# POWER2.net
KiCad netlist of a schematic drawn in Altium Designer
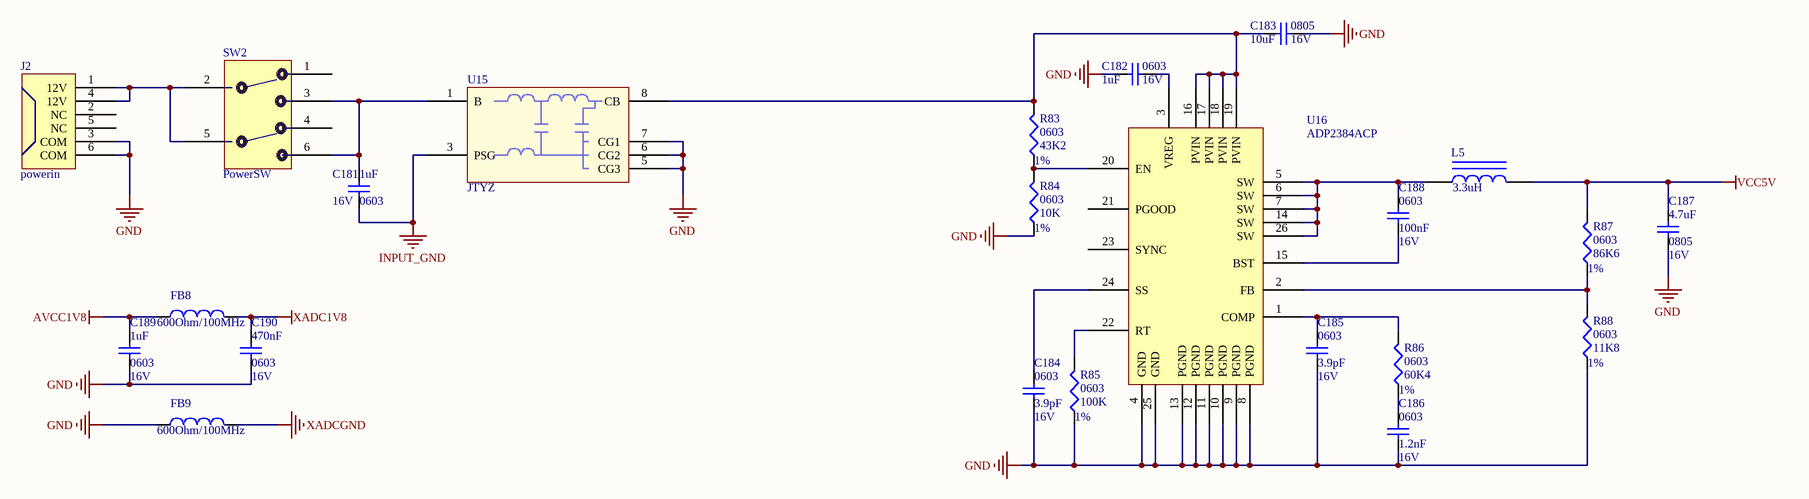
[diagram p0: POWER2.SchDoc]

(export (version "E")
  (design (tool "Eeschema 10.0.6"))
  (components
    (comp (ref "C181")
      (value "1uF")
      (footprint "1608[0603]")
      (description "Capacitor (Semiconductor SIM Model)")
      (fields
        (field (name "PACKAGEREFERENCE") "0603")
        (field (name "V") "16V")
        (field (name "PUBLISHER") "Altium Limited")
      )
      (libsource (lib "Devices") (part "Cap Semi"))
    )
    (comp (ref "C182")
      (value "1uF")
      (footprint "1608[0603]")
      (description "Capacitor (Semiconductor SIM Model)")
      (fields
        (field (name "PACKAGEREFERENCE") "0603")
        (field (name "V") "16V")
        (field (name "PUBLISHER") "Altium Limited")
      )
      (libsource (lib "Devices") (part "Cap Semi"))
    )
    (comp (ref "C183")
      (value "10uF")
      (footprint "2012[0805]")
      (description "Capacitor (Semiconductor SIM Model)")
      (fields
        (field (name "PACKAGEREFERENCE") "0805")
        (field (name "V") "16V")
        (field (name "PUBLISHER") "Altium Limited")
      )
      (libsource (lib "Devices") (part "Cap Semi"))
    )
    (comp (ref "C184")
      (value "3.9pF")
      (footprint "1608[0603]")
      (description "Capacitor (Semiconductor SIM Model)")
      (fields
        (field (name "PACKAGEREFERENCE") "0603")
        (field (name "V") "16V")
        (field (name "PUBLISHER") "Altium Limited")
      )
      (libsource (lib "Devices") (part "Cap Semi"))
    )
    (comp (ref "C185")
      (value "3.9pF")
      (footprint "1608[0603]")
      (description "Capacitor (Semiconductor SIM Model)")
      (fields
        (field (name "PACKAGEREFERENCE") "0603")
        (field (name "V") "16V")
        (field (name "PUBLISHER") "Altium Limited")
      )
      (libsource (lib "Devices") (part "Cap Semi"))
    )
    (comp (ref "C186")
      (value "1.2nF")
      (footprint "1608[0603]")
      (description "Capacitor (Semiconductor SIM Model)")
      (fields
        (field (name "PACKAGEREFERENCE") "0603")
        (field (name "V") "16V")
        (field (name "PUBLISHER") "Altium Limited")
      )
      (libsource (lib "Devices") (part "Cap Semi"))
    )
    (comp (ref "C187")
      (value "4.7uF")
      (footprint "2012[0805]")
      (description "Capacitor (Semiconductor SIM Model)")
      (fields
        (field (name "PACKAGEREFERENCE") "0805")
        (field (name "V") "16V")
        (field (name "PUBLISHER") "Altium Limited")
      )
      (libsource (lib "Devices") (part "Cap Semi"))
    )
    (comp (ref "C188")
      (value "100nF")
      (footprint "1608[0603]")
      (description "Capacitor (Semiconductor SIM Model)")
      (fields
        (field (name "PACKAGEREFERENCE") "0603")
        (field (name "V") "16V")
        (field (name "PUBLISHER") "Altium Limited")
      )
      (libsource (lib "Devices") (part "Cap Semi"))
    )
    (comp (ref "C189")
      (value "1uF")
      (footprint "1608[0603]")
      (description "Capacitor (Semiconductor SIM Model)")
      (fields
        (field (name "PACKAGEREFERENCE") "0603")
        (field (name "V") "16V")
        (field (name "PUBLISHER") "Altium Limited")
      )
      (libsource (lib "Devices") (part "Cap Semi"))
    )
    (comp (ref "C190")
      (value "470nF")
      (footprint "1608[0603]")
      (description "Capacitor (Semiconductor SIM Model)")
      (fields
        (field (name "PACKAGEREFERENCE") "0603")
        (field (name "V") "16V")
        (field (name "PUBLISHER") "Altium Limited")
      )
      (libsource (lib "Devices") (part "Cap Semi"))
    )
    (comp (ref "FB8")
      (value "600Ohm/100MHz")
      (footprint "2012[0805]")
      (description "Inductor")
      (libsource (lib "Miscellaneous Devices") (part "Inductor"))
    )
    (comp (ref "FB9")
      (value "600Ohm/100MHz")
      (footprint "2012[0805]")
      (description "Inductor")
      (libsource (lib "Miscellaneous Devices") (part "Inductor"))
    )
    (comp (ref "J2")
      (value "powerin")
      (footprint "POWER2X3")
      (libsource (lib "Spartan6_LX9_A0") (part "powerin"))
    )
    (comp (ref "L5")
      (value "3.3uH")
      (footprint "SRN4018")
      (description "Magnetic-Core Inductor")
      (fields (field (name "Comment") "Inductor Iron") (field (name "PUBLISHER") "Altium Limited"))
      (libsource (lib "Miscellaneous Devices") (part "Inductor Iron"))
    )
    (comp (ref "R83")
      (value "43K2")
      (footprint "1608[0603]")
      (description "Resistor")
      (fields
        (field (name "PACKAGEREFERENCE") "0603")
        (field (name "AC") "1%")
        (field (name "Comment") "Res3")
        (field (name "PUBLISHER") "Altium Limited")
      )
      (libsource (lib "Miscellaneous Devices") (part "Res3"))
    )
    (comp (ref "R84")
      (value "10K")
      (footprint "1608[0603]")
      (description "Resistor")
      (fields
        (field (name "PACKAGEREFERENCE") "0603")
        (field (name "AC") "1%")
        (field (name "Comment") "Res3")
        (field (name "PUBLISHER") "Altium Limited")
      )
      (libsource (lib "Miscellaneous Devices") (part "Res3"))
    )
    (comp (ref "R85")
      (value "100K")
      (footprint "1608[0603]")
      (description "Resistor")
      (fields
        (field (name "PACKAGEREFERENCE") "0603")
        (field (name "AC") "1%")
        (field (name "Comment") "Res3")
        (field (name "PUBLISHER") "Altium Limited")
      )
      (libsource (lib "Miscellaneous Devices") (part "Res3"))
    )
    (comp (ref "R86")
      (value "60K4")
      (footprint "1608[0603]")
      (description "Resistor")
      (fields
        (field (name "PACKAGEREFERENCE") "0603")
        (field (name "AC") "1%")
        (field (name "Comment") "Res3")
        (field (name "PUBLISHER") "Altium Limited")
      )
      (libsource (lib "Miscellaneous Devices") (part "Res3"))
    )
    (comp (ref "R87")
      (value "86K6")
      (footprint "1608[0603]")
      (description "Resistor")
      (fields
        (field (name "PACKAGEREFERENCE") "0603")
        (field (name "AC") "1%")
        (field (name "Comment") "Res3")
        (field (name "PUBLISHER") "Altium Limited")
      )
      (libsource (lib "Miscellaneous Devices") (part "Res3"))
    )
    (comp (ref "R88")
      (value "11K8")
      (footprint "1608[0603]")
      (description "Resistor")
      (fields
        (field (name "PACKAGEREFERENCE") "0603")
        (field (name "AC") "1%")
        (field (name "Comment") "Res3")
        (field (name "PUBLISHER") "Altium Limited")
      )
      (libsource (lib "Miscellaneous Devices") (part "Res3"))
    )
    (comp (ref "SW2")
      (value "PowerSW")
      (footprint "Power_SW")
      (libsource (lib "Spartan6_LX9_A0") (part "PowerSW"))
    )
    (comp (ref "U15") (value "JTYZ") (footprint "JTYZ") (libsource (lib "Spartan6_LX9_A0") (part "JTYZ")))
    (comp (ref "U16")
      (value "ADP2384ACP")
      (footprint "ADP2384")
      (libsource (lib "Spartan6_LX9_A0") (part "ADP2384ACP"))
    )
  )
  (nets
    (net (code "1") (name "AVCC1V8") (class "Default")
      (node (ref "C189") (pin "1") (pinfunction "1_1") (pintype "passive"))
      (node (ref "FB8") (pin "1") (pinfunction "1_1") (pintype "passive"))
    )
    (net (code "2") (name "GND") (class "Default")
      (node (ref "C182") (pin "2") (pinfunction "2_2") (pintype "passive"))
      (node (ref "C183") (pin "2") (pinfunction "2_2") (pintype "passive"))
      (node (ref "C184") (pin "1") (pinfunction "1_1") (pintype "passive"))
      (node (ref "C185") (pin "1") (pinfunction "1_1") (pintype "passive"))
      (node (ref "C186") (pin "1") (pinfunction "1_1") (pintype "passive"))
      (node (ref "C187") (pin "2") (pinfunction "2_2") (pintype "passive"))
      (node (ref "C189") (pin "2") (pinfunction "2_2") (pintype "passive"))
      (node (ref "C190") (pin "2") (pinfunction "2_2") (pintype "passive"))
      (node (ref "FB9") (pin "1") (pinfunction "1_1") (pintype "passive"))
      (node (ref "J2") (pin "3") (pinfunction "COM_3") (pintype "passive"))
      (node (ref "J2") (pin "6") (pinfunction "COM_6") (pintype "passive"))
      (node (ref "R84") (pin "1") (pinfunction "1_1") (pintype "passive"))
      (node (ref "R85") (pin "1") (pinfunction "1_1") (pintype "passive"))
      (node (ref "R88") (pin "1") (pinfunction "1_1") (pintype "passive"))
      (node (ref "U15") (pin "5") (pinfunction "CG3_5") (pintype "passive"))
      (node (ref "U15") (pin "6") (pinfunction "CG2_6") (pintype "passive"))
      (node (ref "U15") (pin "7") (pinfunction "CG1_7") (pintype "passive"))
      (node (ref "U16") (pin "10") (pinfunction "PGND_10") (pintype "passive"))
      (node (ref "U16") (pin "11") (pinfunction "PGND_11") (pintype "passive"))
      (node (ref "U16") (pin "12") (pinfunction "PGND_12") (pintype "passive"))
      (node (ref "U16") (pin "13") (pinfunction "PGND_13") (pintype "passive"))
      (node (ref "U16") (pin "25") (pinfunction "GND_25") (pintype "passive"))
      (node (ref "U16") (pin "4") (pinfunction "GND_4") (pintype "passive"))
      (node (ref "U16") (pin "8") (pinfunction "PGND_8") (pintype "passive"))
      (node (ref "U16") (pin "9") (pinfunction "PGND_9") (pintype "passive"))
    )
    (net (code "3") (name "INPUT_GND") (class "Default")
      (node (ref "C181") (pin "2") (pinfunction "2_2") (pintype "passive"))
      (node (ref "U15") (pin "3") (pinfunction "PSG_3") (pintype "passive"))
    )
    (net (code "4") (name "Net-(C186-Pad2)") (class "Default")
      (node (ref "C186") (pin "2") (pinfunction "2_2") (pintype "passive"))
      (node (ref "R86") (pin "1") (pinfunction "1_1") (pintype "passive"))
    )
    (net (code "5") (name "Net-(C188-Pad2)") (class "Default")
      (node (ref "C188") (pin "2") (pinfunction "2_2") (pintype "passive"))
      (node (ref "L5") (pin "1") (pinfunction "1_1") (pintype "passive"))
      (node (ref "U16") (pin "14") (pinfunction "SW_14") (pintype "passive"))
      (node (ref "U16") (pin "26") (pinfunction "SW_26") (pintype "passive"))
      (node (ref "U16") (pin "5") (pinfunction "SW_5") (pintype "passive"))
      (node (ref "U16") (pin "6") (pinfunction "SW_6") (pintype "passive"))
      (node (ref "U16") (pin "7") (pinfunction "SW_7") (pintype "passive"))
    )
    (net (code "6") (name "Net-(J2-12V-Pad1)") (class "Default")
      (node (ref "J2") (pin "1") (pinfunction "12V_1") (pintype "passive"))
      (node (ref "J2") (pin "4") (pinfunction "12V_4") (pintype "passive"))
      (node (ref "SW2") (pin "2") (pinfunction "2_2") (pintype "passive"))
      (node (ref "SW2") (pin "5") (pinfunction "5_5") (pintype "passive"))
    )
    (net (code "7") (name "Net-(U15-B)") (class "Default")
      (node (ref "C181") (pin "1") (pinfunction "1_1") (pintype "passive"))
      (node (ref "SW2") (pin "3") (pinfunction "3_3") (pintype "passive"))
      (node (ref "SW2") (pin "6") (pinfunction "6_6") (pintype "passive"))
      (node (ref "U15") (pin "1") (pinfunction "B_1") (pintype "passive"))
    )
    (net (code "8") (name "Net-(U15-CB)") (class "Default")
      (node (ref "C183") (pin "1") (pinfunction "1_1") (pintype "passive"))
      (node (ref "R83") (pin "2") (pinfunction "2_2") (pintype "passive"))
      (node (ref "U15") (pin "8") (pinfunction "CB_8") (pintype "passive"))
      (node (ref "U16") (pin "16") (pinfunction "PVIN_16") (pintype "passive"))
      (node (ref "U16") (pin "17") (pinfunction "PVIN_17") (pintype "passive"))
      (node (ref "U16") (pin "18") (pinfunction "PVIN_18") (pintype "passive"))
      (node (ref "U16") (pin "19") (pinfunction "PVIN_19") (pintype "passive"))
    )
    (net (code "9") (name "Net-(U16-BST)") (class "Default")
      (node (ref "C188") (pin "1") (pinfunction "1_1") (pintype "passive"))
      (node (ref "U16") (pin "15") (pinfunction "BST_15") (pintype "passive"))
    )
    (net (code "10") (name "Net-(U16-COMP)") (class "Default")
      (node (ref "C185") (pin "2") (pinfunction "2_2") (pintype "passive"))
      (node (ref "R86") (pin "2") (pinfunction "2_2") (pintype "passive"))
      (node (ref "U16") (pin "1") (pinfunction "COMP_1") (pintype "passive"))
    )
    (net (code "11") (name "Net-(U16-EN)") (class "Default")
      (node (ref "R83") (pin "1") (pinfunction "1_1") (pintype "passive"))
      (node (ref "R84") (pin "2") (pinfunction "2_2") (pintype "passive"))
      (node (ref "U16") (pin "20") (pinfunction "EN_20") (pintype "passive"))
    )
    (net (code "12") (name "Net-(U16-FB)") (class "Default")
      (node (ref "R87") (pin "1") (pinfunction "1_1") (pintype "passive"))
      (node (ref "R88") (pin "2") (pinfunction "2_2") (pintype "passive"))
      (node (ref "U16") (pin "2") (pinfunction "FB_2") (pintype "passive"))
    )
    (net (code "13") (name "Net-(U16-RT)") (class "Default")
      (node (ref "R85") (pin "2") (pinfunction "2_2") (pintype "passive"))
      (node (ref "U16") (pin "22") (pinfunction "RT_22") (pintype "passive"))
    )
    (net (code "14") (name "Net-(U16-SS)") (class "Default")
      (node (ref "C184") (pin "2") (pinfunction "2_2") (pintype "passive"))
      (node (ref "U16") (pin "24") (pinfunction "SS_24") (pintype "passive"))
    )
    (net (code "15") (name "Net-(U16-VREG)") (class "Default")
      (node (ref "C182") (pin "1") (pinfunction "1_1") (pintype "passive"))
      (node (ref "U16") (pin "3") (pinfunction "VREG_3") (pintype "passive"))
    )
    (net (code "16") (name "VCC5V") (class "Default")
      (node (ref "C187") (pin "1") (pinfunction "1_1") (pintype "passive"))
      (node (ref "L5") (pin "2") (pinfunction "2_2") (pintype "passive"))
      (node (ref "R87") (pin "2") (pinfunction "2_2") (pintype "passive"))
    )
    (net (code "17") (name "XADC1V8") (class "Default")
      (node (ref "C190") (pin "1") (pinfunction "1_1") (pintype "passive"))
      (node (ref "FB8") (pin "2") (pinfunction "2_2") (pintype "passive"))
    )
    (net (code "18") (name "XADCGND") (class "Default")
      (node (ref "FB9") (pin "2") (pinfunction "2_2") (pintype "passive"))
    )
    (net (code "19") (name "unconnected-(J2-NC-Pad2)") (class "Default")
      (node (ref "J2") (pin "2") (pinfunction "NC_2") (pintype "passive"))
    )
    (net (code "20") (name "unconnected-(J2-NC-Pad5)") (class "Default")
      (node (ref "J2") (pin "5") (pinfunction "NC_5") (pintype "passive"))
    )
    (net (code "21") (name "unconnected-(SW2-Pad1)") (class "Default")
      (node (ref "SW2") (pin "1") (pinfunction "1_1") (pintype "passive"))
    )
    (net (code "22") (name "unconnected-(SW2-Pad4)") (class "Default")
      (node (ref "SW2") (pin "4") (pinfunction "4_4") (pintype "passive"))
    )
    (net (code "23") (name "unconnected-(U16-PGOOD-Pad21)") (class "Default")
      (node (ref "U16") (pin "21") (pinfunction "PGOOD_21") (pintype "passive"))
    )
    (net (code "24") (name "unconnected-(U16-SYNC-Pad23)") (class "Default")
      (node (ref "U16") (pin "23") (pinfunction "SYNC_23") (pintype "passive"))
    )
  )
)
